# Arduboy_V3_5-2.net
KiCad netlist of a schematic drawn in Altium Designer
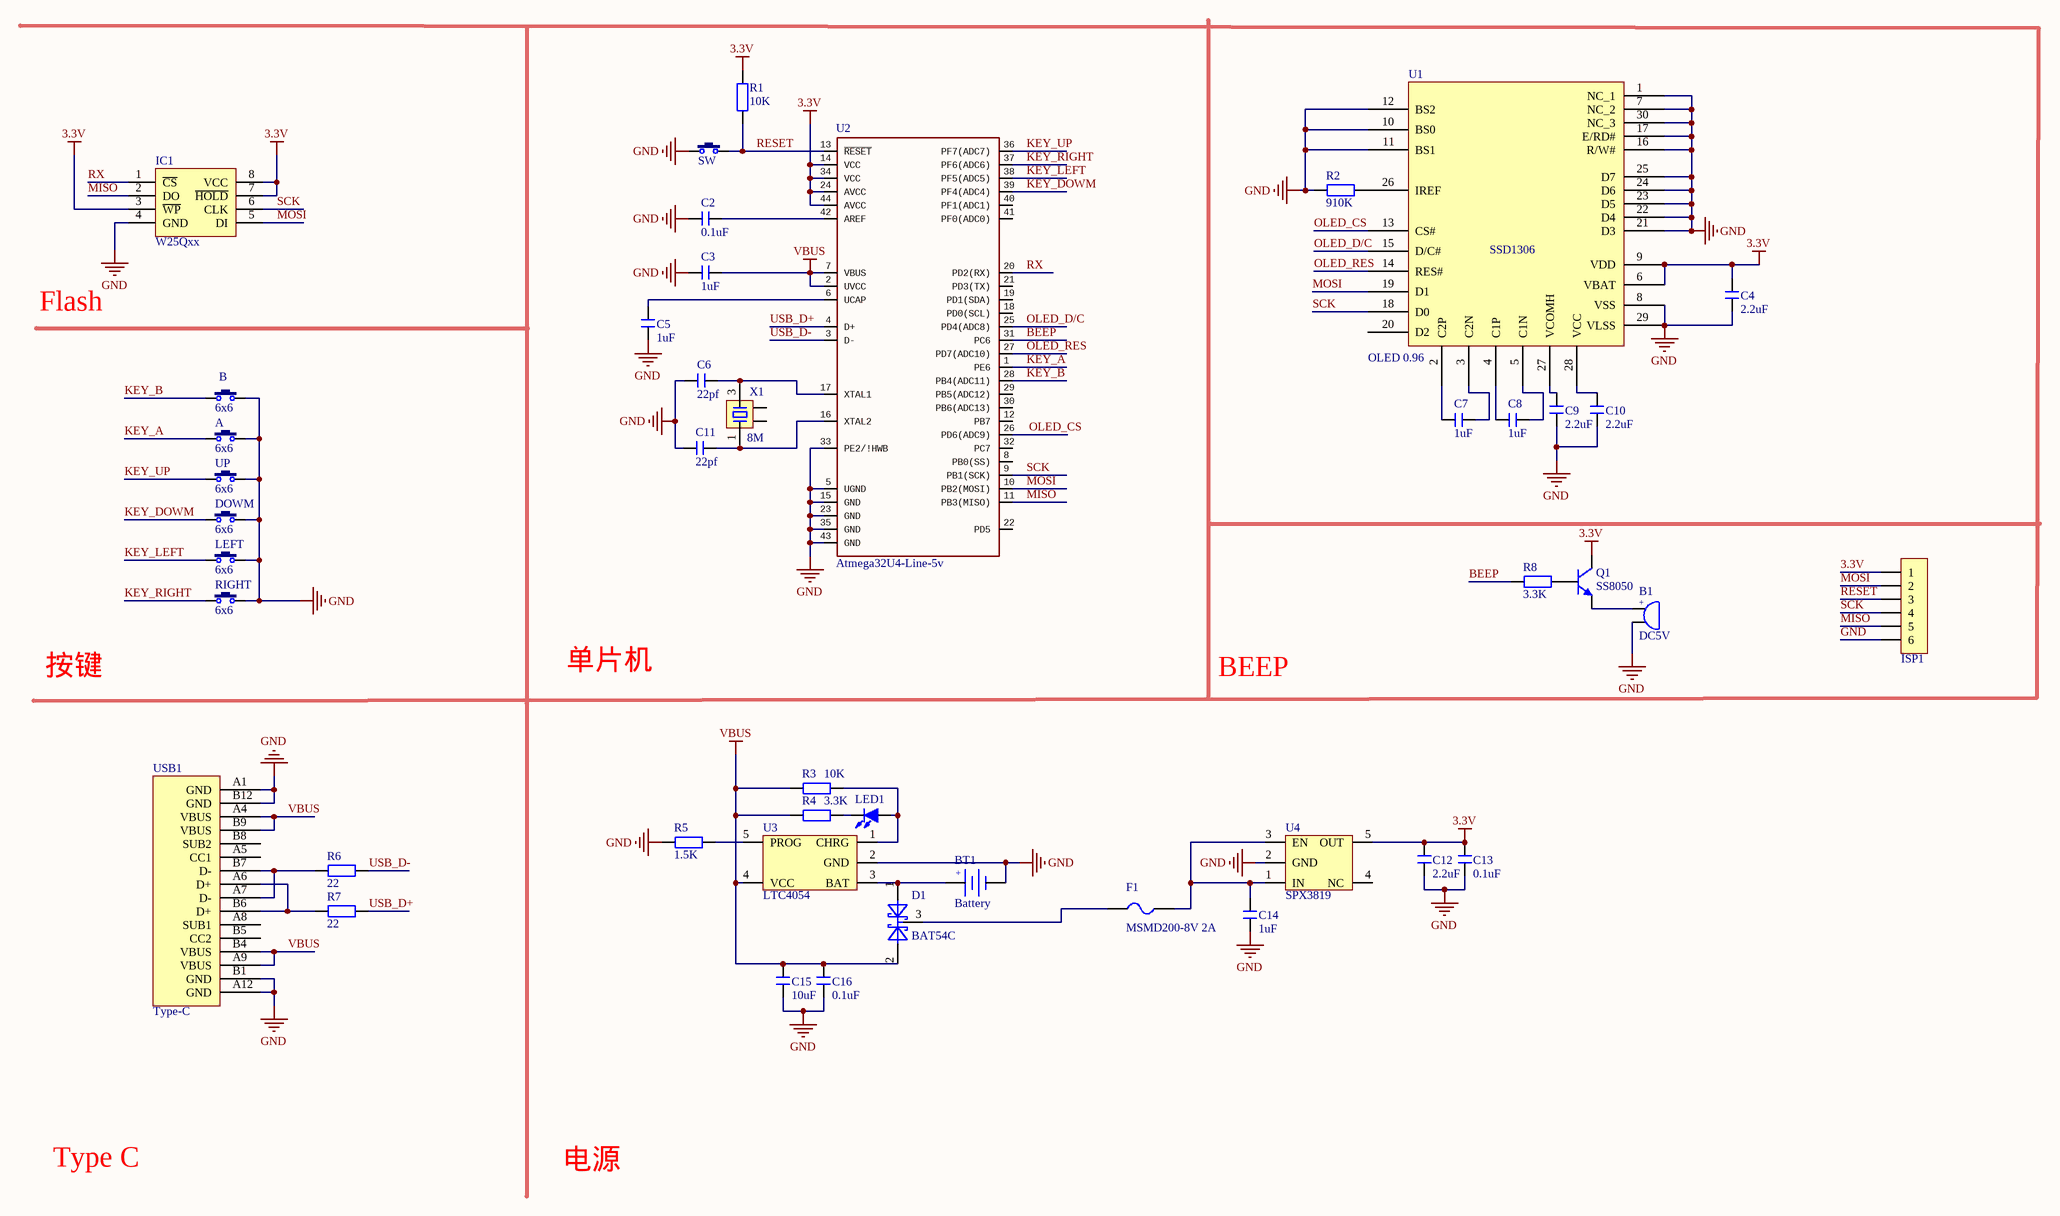
[diagram p0: Arduboy_V3.5-2.SchDoc]

(export (version "E")
  (design (tool "Eeschema 10.0.6"))
  (components
    (comp (ref "A")
      (value "6x6")
      (footprint "SW SMD-4.8*4.8*0.5")
      (description "Arduboy 用")
      (libsource (lib "按键-开关") (part "SW SMD-2"))
    )
    (comp (ref "B")
      (value "6x6")
      (footprint "SW SMD-4.8*4.8*0.5")
      (description "Arduboy 用")
      (libsource (lib "按键-开关") (part "SW SMD-2"))
    )
    (comp (ref "B1")
      (value "DC5V")
      (footprint "BEEP SMD-2")
      (description "蜂鸣器")
      (fields (field (name "版权归属") "黎明电子style"))
      (libsource (lib "未分类器件") (part "BEEP"))
    )
    (comp (ref "BT1")
      (value "Battery")
      (footprint "Li-Bettery SMD")
      (description "锂电池")
      (libsource (lib "未分类器件") (part "Battery"))
    )
    (comp (ref "C2")
      (value "0.1uF")
      (footprint "C 0603")
      (description "无极性贴片电容")
      (fields (field (name "版权归属") "黎明电子style"))
      (libsource (lib "电阻-电容-电感") (part "C"))
    )
    (comp (ref "C3")
      (value "1uF")
      (footprint "C 0603")
      (description "无极性贴片电容")
      (fields (field (name "版权归属") "黎明电子style"))
      (libsource (lib "电阻-电容-电感") (part "C"))
    )
    (comp (ref "C4")
      (value "2.2uF")
      (footprint "C 0603")
      (description "无极性贴片电容")
      (fields (field (name "版权归属") "黎明电子style"))
      (libsource (lib "电阻-电容-电感") (part "C"))
    )
    (comp (ref "C5")
      (value "1uF")
      (footprint "C 0603")
      (description "无极性贴片电容")
      (fields (field (name "版权归属") "黎明电子style"))
      (libsource (lib "电阻-电容-电感") (part "C"))
    )
    (comp (ref "C6")
      (value "22pf")
      (footprint "C 0603")
      (description "无极性贴片电容")
      (fields (field (name "版权归属") "黎明电子style"))
      (libsource (lib "电阻-电容-电感") (part "C"))
    )
    (comp (ref "C7")
      (value "1uF")
      (footprint "C 0603")
      (description "无极性贴片电容")
      (fields (field (name "版权归属") "黎明电子style"))
      (libsource (lib "电阻-电容-电感") (part "C"))
    )
    (comp (ref "C8")
      (value "1uF")
      (footprint "C 0603")
      (description "无极性贴片电容")
      (fields (field (name "版权归属") "黎明电子style"))
      (libsource (lib "电阻-电容-电感") (part "C"))
    )
    (comp (ref "C9")
      (value "2.2uF")
      (footprint "C 0603")
      (description "无极性贴片电容")
      (fields (field (name "版权归属") "黎明电子style"))
      (libsource (lib "电阻-电容-电感") (part "C"))
    )
    (comp (ref "C10")
      (value "2.2uF")
      (footprint "C 0603")
      (description "无极性贴片电容")
      (fields (field (name "版权归属") "黎明电子style"))
      (libsource (lib "电阻-电容-电感") (part "C"))
    )
    (comp (ref "C11")
      (value "22pf")
      (footprint "C 0603")
      (description "无极性贴片电容")
      (fields (field (name "版权归属") "黎明电子style"))
      (libsource (lib "电阻-电容-电感") (part "C"))
    )
    (comp (ref "C12")
      (value "2.2uF")
      (footprint "C 0603")
      (description "无极性贴片电容")
      (fields (field (name "版权归属") "黎明电子style"))
      (libsource (lib "电阻-电容-电感") (part "C"))
    )
    (comp (ref "C13")
      (value "0.1uF")
      (footprint "C 0603")
      (description "无极性贴片电容")
      (fields (field (name "版权归属") "黎明电子style"))
      (libsource (lib "电阻-电容-电感") (part "C"))
    )
    (comp (ref "C14")
      (value "1uF")
      (footprint "C 0603")
      (description "无极性贴片电容")
      (fields (field (name "版权归属") "黎明电子style"))
      (libsource (lib "电阻-电容-电感") (part "C"))
    )
    (comp (ref "C15")
      (value "10uF")
      (footprint "C 0603")
      (description "无极性贴片电容")
      (fields (field (name "版权归属") "黎明电子style"))
      (libsource (lib "电阻-电容-电感") (part "C"))
    )
    (comp (ref "C16")
      (value "0.1uF")
      (footprint "C 0603")
      (description "无极性贴片电容")
      (fields (field (name "版权归属") "黎明电子style"))
      (libsource (lib "电阻-电容-电感") (part "C"))
    )
    (comp (ref "D1")
      (value "BAT54C")
      (footprint "SOT23-3M")
      (description "双肖基特二极管")
      (libsource (lib "二极管-整流桥") (part "BAT54C"))
    )
    (comp (ref "DOWM")
      (value "6x6")
      (footprint "SW SMD-4.8*4.8*0.5")
      (description "Arduboy 用")
      (libsource (lib "按键-开关") (part "SW SMD-2"))
    )
    (comp (ref "F1")
      (value "MSMD200-8V 2A")
      (footprint "FU 0603")
      (description "贴片保险丝")
      (fields (field (name "版权归属") "黎明电子style"))
      (libsource (lib "保险丝-晶振") (part "FU"))
    )
    (comp (ref "IC1")
      (value "W25Qxx")
      (footprint "SOP8W_N")
      (description "外置Flash")
      (fields (field (name "版权归属") "黎明电子style"))
      (libsource (lib "IC芯片") (part "W25Qxx"))
    )
    (comp (ref "ISP1")
      (value "HDR-1X6")
      (footprint "HDR-1X6_H")
      (description "6P接插件")
      (fields (field (name "版权归属") "黎明电子style"))
      (libsource (lib "接插件") (part "Header 6"))
    )
    (comp (ref "LED1")
      (value "~")
      (footprint "LED 0603B")
      (description "贴片LED")
      (fields (field (name "版权归属") "黎明电子style"))
      (libsource (lib "LED") (part "LED-SMD"))
    )
    (comp (ref "LEFT")
      (value "6x6")
      (footprint "SW SMD-4.8*4.8*0.5")
      (description "Arduboy 用")
      (libsource (lib "按键-开关") (part "SW SMD-2"))
    )
    (comp (ref "Q1")
      (value "SS8050")
      (footprint "SOT23-3M")
      (description "高频放大-NPN型")
      (fields (field (name "版权归属") "黎明电子style"))
      (libsource (lib "三极管") (part "8050-SMD"))
    )
    (comp (ref "R1")
      (value "10K")
      (footprint "R 0603")
      (description "贴片电阻")
      (fields (field (name "版权归属") "黎明电子style"))
      (libsource (lib "电阻-电容-电感") (part "R"))
    )
    (comp (ref "R2")
      (value "910K")
      (footprint "R 0603")
      (description "贴片电阻")
      (fields (field (name "版权归属") "黎明电子style"))
      (libsource (lib "电阻-电容-电感") (part "R"))
    )
    (comp (ref "R3")
      (value "10K")
      (footprint "R 0603")
      (description "贴片电阻")
      (fields (field (name "版权归属") "黎明电子style"))
      (libsource (lib "电阻-电容-电感") (part "R"))
    )
    (comp (ref "R4")
      (value "3.3K")
      (footprint "R 0603")
      (description "贴片电阻")
      (fields (field (name "版权归属") "黎明电子style"))
      (libsource (lib "电阻-电容-电感") (part "R"))
    )
    (comp (ref "R5")
      (value "1.5K")
      (footprint "R 0603")
      (description "贴片电阻")
      (fields (field (name "版权归属") "黎明电子style"))
      (libsource (lib "电阻-电容-电感") (part "R"))
    )
    (comp (ref "R6")
      (value "22")
      (footprint "R 0603")
      (description "贴片电阻")
      (fields (field (name "版权归属") "黎明电子style"))
      (libsource (lib "电阻-电容-电感") (part "R"))
    )
    (comp (ref "R7")
      (value "22")
      (footprint "R 0603")
      (description "贴片电阻")
      (fields (field (name "版权归属") "黎明电子style"))
      (libsource (lib "电阻-电容-电感") (part "R"))
    )
    (comp (ref "R8")
      (value "3.3K")
      (footprint "R 0603")
      (description "贴片电阻")
      (fields (field (name "版权归属") "黎明电子style"))
      (libsource (lib "电阻-电容-电感") (part "R"))
    )
    (comp (ref "RIGHT")
      (value "6x6")
      (footprint "SW SMD-4.8*4.8*0.5")
      (description "Arduboy 用")
      (libsource (lib "按键-开关") (part "SW SMD-2"))
    )
    (comp (ref "SW")
      (value "3x6x5")
      (footprint "SW SMD-4.8*4.8*0.5")
      (description "3x6轻触开关")
      (fields (field (name "版权归属") "黎明电子style"))
      (libsource (lib "按键-开关") (part "TSW 3x6"))
    )
    (comp (ref "U1") (value "OLED 0.96") (footprint "OLED 0.96") (libsource (lib "显示器件") (part "OLED 0.96")))
    (comp (ref "U2")
      (value "Atmega32U4-Line-5v")
      (footprint "LQFP-QFN")
      (libsource (lib "Atmel系列单片机") (part "Atmega32U4-Line-5v"))
    )
    (comp (ref "U3")
      (value "LTC4054")
      (footprint "SOT23-5M")
      (description "充电管理")
      (libsource (lib "IC芯片") (part "LTC4054"))
    )
    (comp (ref "U4")
      (value "SPX3819")
      (footprint "SOT23-5N")
      (description "3.3V LDO 稳压")
      (libsource (lib "IC芯片") (part "SPX3819"))
    )
    (comp (ref "UP")
      (value "6x6")
      (footprint "SW SMD-4.8*4.8*0.5")
      (description "Arduboy 用")
      (libsource (lib "按键-开关") (part "SW SMD-2"))
    )
    (comp (ref "USB1")
      (value "Type-C")
      (footprint "Type C 16p")
      (description "USB 3.1  单排16PIN四脚插板(L=7.35) 一体式MD")
      (libsource (lib "接口类") (part "Type-C Socket"))
    )
    (comp (ref "X1")
      (value "8M")
      (footprint "XTAL-3225")
      (description "4脚晶振")
      (fields (field (name "版权归属") "黎明电子style"))
      (libsource (lib "保险丝-晶振") (part "XTAL-4"))
    )
  )
  (nets
    (net (code "1") (name "/BEEP") (class "Default")
      (node (ref "R8") (pin "1") (pinfunction "1_1") (pintype "passive"))
      (node (ref "U2") (pin "31") (pinfunction "PC6_31") (pintype "passive"))
    )
    (net (code "2") (name "/KEY_A") (class "Default")
      (node (ref "A") (pin "1") (pinfunction "1_1") (pintype "passive"))
      (node (ref "U2") (pin "1") (pinfunction "PE6_1") (pintype "passive"))
    )
    (net (code "3") (name "/KEY_B") (class "Default")
      (node (ref "B") (pin "1") (pinfunction "1_1") (pintype "passive"))
      (node (ref "U2") (pin "28") (pinfunction "PB4(ADC11)_28") (pintype "passive"))
    )
    (net (code "4") (name "/KEY_DOWM") (class "Default")
      (node (ref "DOWM") (pin "1") (pinfunction "1_1") (pintype "passive"))
      (node (ref "U2") (pin "39") (pinfunction "PF4(ADC4)_39") (pintype "passive"))
    )
    (net (code "5") (name "/KEY_LEFT") (class "Default")
      (node (ref "LEFT") (pin "1") (pinfunction "1_1") (pintype "passive"))
      (node (ref "U2") (pin "38") (pinfunction "PF5(ADC5)_38") (pintype "passive"))
    )
    (net (code "6") (name "/KEY_RIGHT") (class "Default")
      (node (ref "RIGHT") (pin "1") (pinfunction "1_1") (pintype "passive"))
      (node (ref "U2") (pin "37") (pinfunction "PF6(ADC6)_37") (pintype "passive"))
    )
    (net (code "7") (name "/KEY_UP") (class "Default")
      (node (ref "U2") (pin "36") (pinfunction "PF7(ADC7)_36") (pintype "passive"))
      (node (ref "UP") (pin "1") (pinfunction "1_1") (pintype "passive"))
    )
    (net (code "8") (name "/MISO") (class "Default")
      (node (ref "IC1") (pin "2") (pinfunction "DO_2") (pintype "passive"))
      (node (ref "ISP1") (pin "5") (pinfunction "5_5") (pintype "passive"))
      (node (ref "U2") (pin "11") (pinfunction "PB3(MISO)_11") (pintype "passive"))
    )
    (net (code "9") (name "/MOSI") (class "Default")
      (node (ref "IC1") (pin "5") (pinfunction "DI_5") (pintype "passive"))
      (node (ref "ISP1") (pin "2") (pinfunction "2_2") (pintype "passive"))
      (node (ref "U1") (pin "19") (pinfunction "D1_19") (pintype "passive"))
      (node (ref "U2") (pin "10") (pinfunction "PB2(MOSI)_10") (pintype "passive"))
    )
    (net (code "10") (name "/OLED_CS") (class "Default")
      (node (ref "U1") (pin "13") (pinfunction "CS#_13") (pintype "passive"))
      (node (ref "U2") (pin "26") (pinfunction "PD6(ADC9)_26") (pintype "passive"))
    )
    (net (code "11") (name "/OLED_D{slash}C") (class "Default")
      (node (ref "U1") (pin "15") (pinfunction "D/C#_15") (pintype "passive"))
      (node (ref "U2") (pin "25") (pinfunction "PD4(ADC8)_25") (pintype "passive"))
    )
    (net (code "12") (name "/OLED_RES") (class "Default")
      (node (ref "U1") (pin "14") (pinfunction "RES#_14") (pintype "passive"))
      (node (ref "U2") (pin "27") (pinfunction "PD7(ADC10)_27") (pintype "passive"))
    )
    (net (code "13") (name "/RESET") (class "Default")
      (node (ref "ISP1") (pin "3") (pinfunction "3_3") (pintype "passive"))
      (node (ref "R1") (pin "1") (pinfunction "1_1") (pintype "passive"))
      (node (ref "SW") (pin "2") (pinfunction "2_2") (pintype "passive"))
      (node (ref "U2") (pin "13") (pinfunction "~{RESET}_13") (pintype "passive"))
    )
    (net (code "14") (name "/RX") (class "Default")
      (node (ref "IC1") (pin "1") (pinfunction "~{CS}_1") (pintype "passive"))
      (node (ref "U2") (pin "20") (pinfunction "PD2(RX)_20") (pintype "passive"))
    )
    (net (code "15") (name "/SCK") (class "Default")
      (node (ref "IC1") (pin "6") (pinfunction "CLK_6") (pintype "passive"))
      (node (ref "ISP1") (pin "4") (pinfunction "4_4") (pintype "passive"))
      (node (ref "U1") (pin "18") (pinfunction "D0_18") (pintype "passive"))
      (node (ref "U2") (pin "9") (pinfunction "PB1(SCK)_9") (pintype "passive"))
    )
    (net (code "16") (name "/USB_D+") (class "Default")
      (node (ref "R7") (pin "1") (pinfunction "1_1") (pintype "passive"))
      (node (ref "U2") (pin "4") (pinfunction "D+_4") (pintype "passive"))
    )
    (net (code "17") (name "/USB_D-") (class "Default")
      (node (ref "R6") (pin "1") (pinfunction "1_1") (pintype "passive"))
      (node (ref "U2") (pin "3") (pinfunction "D-_3") (pintype "passive"))
    )
    (net (code "18") (name "3.3V") (class "Default")
      (node (ref "C12") (pin "2") (pinfunction "2_2") (pintype "passive"))
      (node (ref "C13") (pin "2") (pinfunction "2_2") (pintype "passive"))
      (node (ref "C4") (pin "2") (pinfunction "2_2") (pintype "passive"))
      (node (ref "IC1") (pin "3") (pinfunction "~{WP}_3") (pintype "passive"))
      (node (ref "IC1") (pin "7") (pinfunction "~{HOLD}_7") (pintype "passive"))
      (node (ref "IC1") (pin "8") (pinfunction "VCC_8") (pintype "passive"))
      (node (ref "ISP1") (pin "1") (pinfunction "1_1") (pintype "passive"))
      (node (ref "Q1") (pin "3") (pinfunction "C_3") (pintype "passive"))
      (node (ref "R1") (pin "2") (pinfunction "2_2") (pintype "passive"))
      (node (ref "U1") (pin "6") (pinfunction "VBAT_6") (pintype "passive"))
      (node (ref "U1") (pin "9") (pinfunction "VDD_9") (pintype "passive"))
      (node (ref "U2") (pin "14") (pinfunction "VCC_14") (pintype "passive"))
      (node (ref "U2") (pin "24") (pinfunction "AVCC_24") (pintype "passive"))
      (node (ref "U2") (pin "34") (pinfunction "VCC_34") (pintype "passive"))
      (node (ref "U2") (pin "44") (pinfunction "AVCC_44") (pintype "passive"))
      (node (ref "U4") (pin "5") (pinfunction "OUT_5") (pintype "passive"))
    )
    (net (code "19") (name "GND") (class "Default")
      (node (ref "A") (pin "2") (pinfunction "2_2") (pintype "passive"))
      (node (ref "B") (pin "2") (pinfunction "2_2") (pintype "passive"))
      (node (ref "B1") (pin "2") (pinfunction "2_2") (pintype "passive"))
      (node (ref "BT1") (pin "2") (pintype "passive"))
      (node (ref "C10") (pin "1") (pinfunction "1_1") (pintype "passive"))
      (node (ref "C11") (pin "1") (pinfunction "1_1") (pintype "passive"))
      (node (ref "C12") (pin "1") (pinfunction "1_1") (pintype "passive"))
      (node (ref "C13") (pin "1") (pinfunction "1_1") (pintype "passive"))
      (node (ref "C14") (pin "1") (pinfunction "1_1") (pintype "passive"))
      (node (ref "C15") (pin "1") (pinfunction "1_1") (pintype "passive"))
      (node (ref "C16") (pin "1") (pinfunction "1_1") (pintype "passive"))
      (node (ref "C2") (pin "1") (pinfunction "1_1") (pintype "passive"))
      (node (ref "C3") (pin "1") (pinfunction "1_1") (pintype "passive"))
      (node (ref "C4") (pin "1") (pinfunction "1_1") (pintype "passive"))
      (node (ref "C5") (pin "2") (pinfunction "2_2") (pintype "passive"))
      (node (ref "C6") (pin "1") (pinfunction "1_1") (pintype "passive"))
      (node (ref "C9") (pin "1") (pinfunction "1_1") (pintype "passive"))
      (node (ref "DOWM") (pin "2") (pinfunction "2_2") (pintype "passive"))
      (node (ref "IC1") (pin "4") (pinfunction "GND_4") (pintype "passive"))
      (node (ref "ISP1") (pin "6") (pinfunction "6_6") (pintype "passive"))
      (node (ref "LEFT") (pin "2") (pinfunction "2_2") (pintype "passive"))
      (node (ref "R2") (pin "1") (pinfunction "1_1") (pintype "passive"))
      (node (ref "R5") (pin "2") (pinfunction "2_2") (pintype "passive"))
      (node (ref "RIGHT") (pin "2") (pinfunction "2_2") (pintype "passive"))
      (node (ref "SW") (pin "1") (pinfunction "1_1") (pintype "passive"))
      (node (ref "U1") (pin "1") (pinfunction "NC_1_1") (pintype "passive"))
      (node (ref "U1") (pin "10") (pinfunction "BS0_10") (pintype "passive"))
      (node (ref "U1") (pin "11") (pinfunction "BS1_11") (pintype "passive"))
      (node (ref "U1") (pin "12") (pinfunction "BS2_12") (pintype "passive"))
      (node (ref "U1") (pin "16") (pinfunction "R/W#_16") (pintype "passive"))
      (node (ref "U1") (pin "17") (pinfunction "E/RD#_17") (pintype "passive"))
      (node (ref "U1") (pin "21") (pinfunction "D3_21") (pintype "passive"))
      (node (ref "U1") (pin "22") (pinfunction "D4_22") (pintype "passive"))
      (node (ref "U1") (pin "23") (pinfunction "D5_23") (pintype "passive"))
      (node (ref "U1") (pin "24") (pinfunction "D6_24") (pintype "passive"))
      (node (ref "U1") (pin "25") (pinfunction "D7_25") (pintype "passive"))
      (node (ref "U1") (pin "29") (pinfunction "VLSS_29") (pintype "passive"))
      (node (ref "U1") (pin "30") (pinfunction "NC_3_30") (pintype "passive"))
      (node (ref "U1") (pin "7") (pinfunction "NC_2_7") (pintype "passive"))
      (node (ref "U1") (pin "8") (pinfunction "VSS_8") (pintype "passive"))
      (node (ref "U2") (pin "15") (pinfunction "GND_15") (pintype "passive"))
      (node (ref "U2") (pin "23") (pinfunction "GND_23") (pintype "passive"))
      (node (ref "U2") (pin "33") (pinfunction "PE2/!HWB_33") (pintype "passive"))
      (node (ref "U2") (pin "35") (pinfunction "GND_35") (pintype "passive"))
      (node (ref "U2") (pin "43") (pinfunction "GND_43") (pintype "passive"))
      (node (ref "U2") (pin "5") (pinfunction "UGND_5") (pintype "passive"))
      (node (ref "U3") (pin "2") (pinfunction "GND_2") (pintype "passive"))
      (node (ref "U4") (pin "2") (pinfunction "GND_2") (pintype "passive"))
      (node (ref "UP") (pin "2") (pinfunction "2_2") (pintype "passive"))
      (node (ref "USB1") (pin "A1") (pinfunction "GND_A1") (pintype "passive"))
      (node (ref "USB1") (pin "A12") (pinfunction "GND_A12") (pintype "passive"))
      (node (ref "USB1") (pin "B1") (pinfunction "GND_B1") (pintype "passive"))
      (node (ref "USB1") (pin "B12") (pinfunction "GND_B12") (pintype "passive"))
    )
    (net (code "20") (name "Net-(D1-Pad3)") (class "Default")
      (node (ref "D1") (pin "3") (pintype "passive"))
      (node (ref "F1") (pin "1") (pinfunction "1_1") (pintype "passive"))
    )
    (net (code "21") (name "Net-(LED1-A)") (class "Default")
      (node (ref "LED1") (pin "1") (pinfunction "A_1") (pintype "passive"))
      (node (ref "R3") (pin "2") (pinfunction "2_2") (pintype "passive"))
      (node (ref "U3") (pin "1") (pinfunction "CHRG_1") (pintype "passive"))
    )
    (net (code "22") (name "Net-(LED1-K)") (class "Default")
      (node (ref "LED1") (pin "2") (pinfunction "K_2") (pintype "passive"))
      (node (ref "R4") (pin "1") (pinfunction "1_1") (pintype "passive"))
    )
    (net (code "23") (name "Net-(Q1-B)") (class "Default")
      (node (ref "Q1") (pin "1") (pinfunction "B_1") (pintype "passive"))
      (node (ref "R8") (pin "2") (pinfunction "2_2") (pintype "passive"))
    )
    (net (code "24") (name "Net-(Q1-E)") (class "Default")
      (node (ref "B1") (pin "1") (pinfunction "1_1") (pintype "passive"))
      (node (ref "Q1") (pin "2") (pinfunction "E_2") (pintype "passive"))
    )
    (net (code "25") (name "Net-(R6-Pad2)") (class "Default")
      (node (ref "R6") (pin "2") (pinfunction "2_2") (pintype "passive"))
      (node (ref "USB1") (pin "A7") (pinfunction "D-_A7") (pintype "passive"))
      (node (ref "USB1") (pin "B7") (pinfunction "D-_B7") (pintype "passive"))
    )
    (net (code "26") (name "Net-(R7-Pad2)") (class "Default")
      (node (ref "R7") (pin "2") (pinfunction "2_2") (pintype "passive"))
      (node (ref "USB1") (pin "A6") (pinfunction "D+_A6") (pintype "passive"))
      (node (ref "USB1") (pin "B6") (pinfunction "D+_B6") (pintype "passive"))
    )
    (net (code "27") (name "Net-(U1-C1N)") (class "Default")
      (node (ref "C8") (pin "2") (pinfunction "2_2") (pintype "passive"))
      (node (ref "U1") (pin "5") (pinfunction "C1N_5") (pintype "passive"))
    )
    (net (code "28") (name "Net-(U1-C1P)") (class "Default")
      (node (ref "C8") (pin "1") (pinfunction "1_1") (pintype "passive"))
      (node (ref "U1") (pin "4") (pinfunction "C1P_4") (pintype "passive"))
    )
    (net (code "29") (name "Net-(U1-C2N)") (class "Default")
      (node (ref "C7") (pin "2") (pinfunction "2_2") (pintype "passive"))
      (node (ref "U1") (pin "3") (pinfunction "C2N_3") (pintype "passive"))
    )
    (net (code "30") (name "Net-(U1-C2P)") (class "Default")
      (node (ref "C7") (pin "1") (pinfunction "1_1") (pintype "passive"))
      (node (ref "U1") (pin "2") (pinfunction "C2P_2") (pintype "passive"))
    )
    (net (code "31") (name "Net-(U1-IREF)") (class "Default")
      (node (ref "R2") (pin "2") (pinfunction "2_2") (pintype "passive"))
      (node (ref "U1") (pin "26") (pinfunction "IREF_26") (pintype "passive"))
    )
    (net (code "32") (name "Net-(U1-VCC)") (class "Default")
      (node (ref "C10") (pin "2") (pinfunction "2_2") (pintype "passive"))
      (node (ref "U1") (pin "28") (pinfunction "VCC_28") (pintype "passive"))
    )
    (net (code "33") (name "Net-(U1-VCOMH)") (class "Default")
      (node (ref "C9") (pin "2") (pinfunction "2_2") (pintype "passive"))
      (node (ref "U1") (pin "27") (pinfunction "VCOMH_27") (pintype "passive"))
    )
    (net (code "34") (name "Net-(U2-AREF)") (class "Default")
      (node (ref "C2") (pin "2") (pinfunction "2_2") (pintype "passive"))
      (node (ref "U2") (pin "42") (pinfunction "AREF_42") (pintype "passive"))
    )
    (net (code "35") (name "Net-(U2-UCAP)") (class "Default")
      (node (ref "C5") (pin "1") (pinfunction "1_1") (pintype "passive"))
      (node (ref "U2") (pin "6") (pinfunction "UCAP_6") (pintype "passive"))
    )
    (net (code "36") (name "Net-(U2-XTAL1)") (class "Default")
      (node (ref "C6") (pin "2") (pinfunction "2_2") (pintype "passive"))
      (node (ref "U2") (pin "17") (pinfunction "XTAL1_17") (pintype "passive"))
      (node (ref "X1") (pin "3") (pinfunction "3_3") (pintype "passive"))
    )
    (net (code "37") (name "Net-(U2-XTAL2)") (class "Default")
      (node (ref "C11") (pin "2") (pinfunction "2_2") (pintype "passive"))
      (node (ref "U2") (pin "16") (pinfunction "XTAL2_16") (pintype "passive"))
      (node (ref "X1") (pin "1") (pinfunction "1_1") (pintype "passive"))
    )
    (net (code "38") (name "Net-(U3-BAT)") (class "Default")
      (node (ref "BT1") (pin "1") (pintype "passive"))
      (node (ref "D1") (pin "1") (pintype "passive"))
      (node (ref "U3") (pin "3") (pinfunction "BAT_3") (pintype "passive"))
    )
    (net (code "39") (name "Net-(U3-PROG)") (class "Default")
      (node (ref "R5") (pin "1") (pinfunction "1_1") (pintype "passive"))
      (node (ref "U3") (pin "5") (pinfunction "PROG_5") (pintype "passive"))
    )
    (net (code "40") (name "Net-(U4-EN)") (class "Default")
      (node (ref "C14") (pin "2") (pinfunction "2_2") (pintype "passive"))
      (node (ref "F1") (pin "2") (pinfunction "2_2") (pintype "passive"))
      (node (ref "U4") (pin "1") (pinfunction "IN_1") (pintype "passive"))
      (node (ref "U4") (pin "3") (pinfunction "EN_3") (pintype "passive"))
    )
    (net (code "41") (name "VBUS") (class "Default")
      (node (ref "C15") (pin "2") (pinfunction "2_2") (pintype "passive"))
      (node (ref "C16") (pin "2") (pinfunction "2_2") (pintype "passive"))
      (node (ref "C3") (pin "2") (pinfunction "2_2") (pintype "passive"))
      (node (ref "D1") (pin "2") (pintype "passive"))
      (node (ref "R3") (pin "1") (pinfunction "1_1") (pintype "passive"))
      (node (ref "R4") (pin "2") (pinfunction "2_2") (pintype "passive"))
      (node (ref "U2") (pin "2") (pinfunction "UVCC_2") (pintype "passive"))
      (node (ref "U2") (pin "7") (pinfunction "VBUS_7") (pintype "passive"))
      (node (ref "U3") (pin "4") (pinfunction "VCC_4") (pintype "passive"))
      (node (ref "USB1") (pin "A4") (pinfunction "VBUS_A4") (pintype "passive"))
      (node (ref "USB1") (pin "A9") (pinfunction "VBUS_A9") (pintype "passive"))
      (node (ref "USB1") (pin "B4") (pinfunction "VBUS_B4") (pintype "passive"))
      (node (ref "USB1") (pin "B9") (pinfunction "VBUS_B9") (pintype "passive"))
    )
    (net (code "42") (name "unconnected-(U1-D2-Pad20)") (class "Default")
      (node (ref "U1") (pin "20") (pinfunction "D2_20") (pintype "passive"))
    )
    (net (code "43") (name "unconnected-(U2-PB0(SS)-Pad8)") (class "Default")
      (node (ref "U2") (pin "8") (pinfunction "PB0(SS)_8") (pintype "passive"))
    )
    (net (code "44") (name "unconnected-(U2-PB5(ADC12)-Pad29)") (class "Default")
      (node (ref "U2") (pin "29") (pinfunction "PB5(ADC12)_29") (pintype "passive"))
    )
    (net (code "45") (name "unconnected-(U2-PB6(ADC13)-Pad30)") (class "Default")
      (node (ref "U2") (pin "30") (pinfunction "PB6(ADC13)_30") (pintype "passive"))
    )
    (net (code "46") (name "unconnected-(U2-PB7-Pad12)") (class "Default")
      (node (ref "U2") (pin "12") (pinfunction "PB7_12") (pintype "passive"))
    )
    (net (code "47") (name "unconnected-(U2-PC7-Pad32)") (class "Default")
      (node (ref "U2") (pin "32") (pinfunction "PC7_32") (pintype "passive"))
    )
    (net (code "48") (name "unconnected-(U2-PD0(SCL)-Pad18)") (class "Default")
      (node (ref "U2") (pin "18") (pinfunction "PD0(SCL)_18") (pintype "passive"))
    )
    (net (code "49") (name "unconnected-(U2-PD1(SDA)-Pad19)") (class "Default")
      (node (ref "U2") (pin "19") (pinfunction "PD1(SDA)_19") (pintype "passive"))
    )
    (net (code "50") (name "unconnected-(U2-PD3(TX)-Pad21)") (class "Default")
      (node (ref "U2") (pin "21") (pinfunction "PD3(TX)_21") (pintype "passive"))
    )
    (net (code "51") (name "unconnected-(U2-PD5-Pad22)") (class "Default")
      (node (ref "U2") (pin "22") (pinfunction "PD5_22") (pintype "passive"))
    )
    (net (code "52") (name "unconnected-(U2-PF0(ADC0)-Pad41)") (class "Default")
      (node (ref "U2") (pin "41") (pinfunction "PF0(ADC0)_41") (pintype "passive"))
    )
    (net (code "53") (name "unconnected-(U2-PF1(ADC1)-Pad40)") (class "Default")
      (node (ref "U2") (pin "40") (pinfunction "PF1(ADC1)_40") (pintype "passive"))
    )
    (net (code "54") (name "unconnected-(U4-NC-Pad4)") (class "Default")
      (node (ref "U4") (pin "4") (pinfunction "NC_4") (pintype "passive"))
    )
    (net (code "55") (name "unconnected-(USB1-CC1-PadA5)") (class "Default")
      (node (ref "USB1") (pin "A5") (pinfunction "CC1_A5") (pintype "passive"))
    )
    (net (code "56") (name "unconnected-(USB1-CC2-PadB5)") (class "Default")
      (node (ref "USB1") (pin "B5") (pinfunction "CC2_B5") (pintype "passive"))
    )
    (net (code "57") (name "unconnected-(USB1-SUB1-PadA8)") (class "Default")
      (node (ref "USB1") (pin "A8") (pinfunction "SUB1_A8") (pintype "passive"))
    )
    (net (code "58") (name "unconnected-(USB1-SUB2-PadB8)") (class "Default")
      (node (ref "USB1") (pin "B8") (pinfunction "SUB2_B8") (pintype "passive"))
    )
    (net (code "59") (name "unconnected-(X1-Pad2)") (class "Default")
      (node (ref "X1") (pin "2") (pinfunction "2_2") (pintype "passive"))
    )
    (net (code "60") (name "unconnected-(X1-Pad4)") (class "Default")
      (node (ref "X1") (pin "4") (pinfunction "4_4") (pintype "passive"))
    )
  )
)
